# Sheet1.net
KiCad netlist of a schematic drawn in Altium Designer
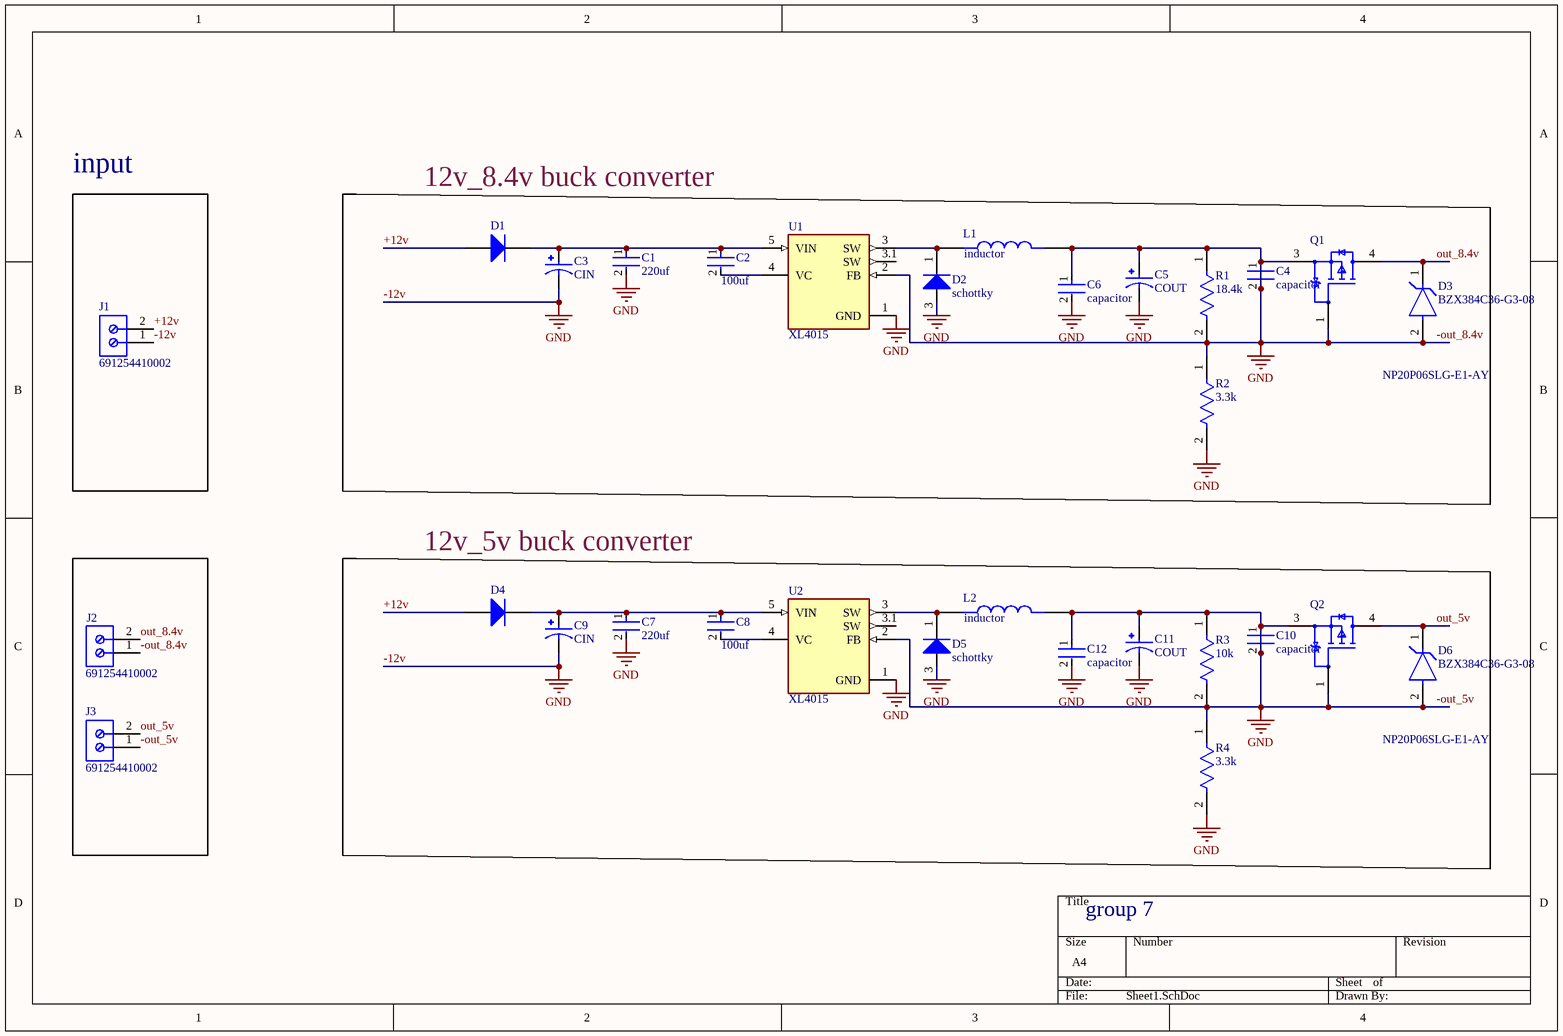
[diagram p0: Sheet1.SchDoc]

(export (version "E")
  (design (tool "Eeschema 10.0.6"))
  (components
    (comp (ref "C1")
      (value "220uf")
      (footprint "FP-GRM43D-0_4-IPC_A")
      (description "Chip Multilayer Ceramic Capacitors for General Purpose, 1812, 0.10uF, X7R, 15%, 10%, 630V")
      (fields (field (name "TOLERANCE") "10%") (field (name "VOLTAGE") "630V"))
      (libsource (lib "Altium Content Vault") (part "02cd4be3c70576c341d710602a673aa"))
    )
    (comp (ref "C2")
      (value "100uf")
      (footprint "FP-GRM43D-0_4-IPC_A")
      (description "Chip Multilayer Ceramic Capacitors for General Purpose, 1812, 0.10uF, X7R, 15%, 10%, 630V")
      (fields (field (name "TOLERANCE") "10%") (field (name "VOLTAGE") "630V"))
      (libsource (lib "Altium Content Vault") (part "02cd4be3c70576c341d710602a673aa"))
    )
    (comp (ref "C3")
      (value "CIN")
      (footprint "CAPPRD500W60D1250H1500:CAPPRD500W60D1250H1500")
      (description "220F 50V Aluminum Electrolytic Capacitors Radial, Can 5000 Hrs @ 105C")
      (fields (field (name "MP") "EEU-FC1H221S") (field (name "MF") "Panasonic Electronic"))
      (libsource (lib "EEUFC1H221S") (part "EEUFC1H221S"))
    )
    (comp (ref "C4")
      (value "capacitor")
      (footprint "FP-GRM43D-0_4-IPC_A")
      (description "Chip Multilayer Ceramic Capacitors for General Purpose, 1812, 0.10uF, X7R, 15%, 10%, 630V")
      (fields (field (name "TOLERANCE") "10%") (field (name "VOLTAGE") "630V"))
      (libsource (lib "Altium Content Vault") (part "02cd4be3c70576c341d710602a673aa"))
    )
    (comp (ref "C5")
      (value "COUT")
      (footprint "CAPPRD500W60D1250H1500:CAPPRD500W60D1250H1500")
      (description "330F 25V Aluminum Electrolytic Capacitors Radial, Can 5000 Hrs @ 105C")
      (fields (field (name "MP") "EEU-FC1H221S") (field (name "MF") "Panasonic Electronic"))
      (libsource (lib "EEUFC1H221S") (part "EEUFC1H221S"))
    )
    (comp (ref "C6")
      (value "capacitor")
      (footprint "FP-GRM43D-0_4-IPC_A")
      (description "Chip Multilayer Ceramic Capacitors for General Purpose, 1812, 0.10uF, X7R, 15%, 10%, 630V")
      (fields (field (name "TOLERANCE") "10%") (field (name "VOLTAGE") "630V"))
      (libsource (lib "Altium Content Vault") (part "02cd4be3c70576c341d710602a673aa"))
    )
    (comp (ref "C7")
      (value "220uf")
      (footprint "FP-GRM43D-0_4-IPC_A")
      (description "Chip Multilayer Ceramic Capacitors for General Purpose, 1812, 0.10uF, X7R, 15%, 10%, 630V")
      (fields (field (name "TOLERANCE") "10%") (field (name "VOLTAGE") "630V"))
      (libsource (lib "Altium Content Vault") (part "02cd4be3c70576c341d710602a673aa"))
    )
    (comp (ref "C8")
      (value "100uf")
      (footprint "FP-GRM43D-0_4-IPC_A")
      (description "Chip Multilayer Ceramic Capacitors for General Purpose, 1812, 0.10uF, X7R, 15%, 10%, 630V")
      (fields (field (name "TOLERANCE") "10%") (field (name "VOLTAGE") "630V"))
      (libsource (lib "Altium Content Vault") (part "02cd4be3c70576c341d710602a673aa"))
    )
    (comp (ref "C9")
      (value "CIN")
      (footprint "CAPPRD500W60D1250H1500:CAPPRD500W60D1250H1500")
      (description "220F 50V Aluminum Electrolytic Capacitors Radial, Can 5000 Hrs @ 105C")
      (fields (field (name "MP") "EEU-FC1H221S") (field (name "MF") "Panasonic Electronic"))
      (libsource (lib "EEUFC1H221S") (part "EEUFC1H221S"))
    )
    (comp (ref "C10")
      (value "capacitor")
      (footprint "FP-GRM43D-0_4-IPC_A")
      (description "Chip Multilayer Ceramic Capacitors for General Purpose, 1812, 0.10uF, X7R, 15%, 10%, 630V")
      (fields (field (name "TOLERANCE") "10%") (field (name "VOLTAGE") "630V"))
      (libsource (lib "Altium Content Vault") (part "02cd4be3c70576c341d710602a673aa"))
    )
    (comp (ref "C11")
      (value "COUT")
      (footprint "CAPPRD500W60D1250H1500:CAPPRD500W60D1250H1500")
      (description "330F 25V Aluminum Electrolytic Capacitors Radial, Can 5000 Hrs @ 105C")
      (fields (field (name "MP") "EEU-FC1H221S") (field (name "MF") "Panasonic Electronic"))
      (libsource (lib "EEUFC1H221S") (part "EEUFC1H221S"))
    )
    (comp (ref "C12")
      (value "capacitor")
      (footprint "FP-GRM43D-0_4-IPC_A")
      (description "Chip Multilayer Ceramic Capacitors for General Purpose, 1812, 0.10uF, X7R, 15%, 10%, 630V")
      (fields (field (name "TOLERANCE") "10%") (field (name "VOLTAGE") "630V"))
      (libsource (lib "Altium Content Vault") (part "02cd4be3c70576c341d710602a673aa"))
    )
    (comp (ref "D1") (value "Diode") (libsource (lib "Simulation Generic Components") (part "Diode")))
    (comp (ref "D2")
      (value "schottky")
      (footprint "ONSC-TO-220-2-221B-04_E")
      (description "SWITCHMODE(TM) Power Rectifier, 2-Pin TO-220, Pb-Free, Tube")
      (fields (field (name "MANUFACTURER") "On Semiconductor") (field (name "PARTNUMBER") "MBR1045G"))
      (libsource (lib "Altium Content Vault") (part "ONSC-D-K1A3-2_A"))
    )
    (comp (ref "D3")
      (value "BZX384C36-G3-08")
      (footprint "FP-S8-V-3910_02-001-MFG")
      (description "BZX384C36-G3-08 Zener Diode Sod3235%, 36V, 0.2W")
      (fields (field (name "TOLERANCE") "5%"))
      (libsource (lib "Altium Content Vault") (part "f813f71cba58e380607f5dd3caf9714"))
    )
    (comp (ref "D4") (value "Diode") (libsource (lib "Simulation Generic Components") (part "Diode")))
    (comp (ref "D5")
      (value "schottky")
      (footprint "ONSC-TO-220-2-221B-04_E")
      (description "SWITCHMODE(TM) Power Rectifier, 2-Pin TO-220, Pb-Free, Tube")
      (fields (field (name "MANUFACTURER") "On Semiconductor") (field (name "PARTNUMBER") "MBR1045G"))
      (libsource (lib "Altium Content Vault") (part "ONSC-D-K1A3-2_A"))
    )
    (comp (ref "D6")
      (value "BZX384C36-G3-08")
      (footprint "FP-S8-V-3910_02-001-MFG")
      (description "BZX384C36-G3-08 Zener Diode Sod3235%, 36V, 0.2W")
      (fields (field (name "TOLERANCE") "5%"))
      (libsource (lib "Altium Content Vault") (part "f813f71cba58e380607f5dd3caf9714"))
    )
    (comp (ref "J1")
      (value "691254410002")
      (footprint "691254410002")
      (libsource (lib "Altium Content Vault") (part "TBL - 1R - 02P - Screw"))
    )
    (comp (ref "J2")
      (value "691254410002")
      (footprint "691254410002")
      (libsource (lib "Altium Content Vault") (part "TBL - 1R - 02P - Screw"))
    )
    (comp (ref "J3")
      (value "691254410002")
      (footprint "691254410002")
      (libsource (lib "Altium Content Vault") (part "TBL - 1R - 02P - Screw"))
    )
    (comp (ref "L1")
      (value "inductor")
      (footprint "IND_XAL6060-223MEC")
      (description "22 ÂµH Shielded Molded Inductor 5 A 60.63mOhm Max Nonstandard")
      (fields (field (name "MF") "Coilcraft") (field (name "MP") "XAL6060-223MEC"))
      (libsource (lib "XAL6060-223MEC") (part "XAL6060-223MEC"))
    )
    (comp (ref "L2")
      (value "inductor")
      (footprint "IND_XAL6060-223MEC")
      (description "22 ÂµH Shielded Molded Inductor 5 A 60.63mOhm Max Nonstandard")
      (fields (field (name "MF") "Coilcraft") (field (name "MP") "XAL6060-223MEC"))
      (libsource (lib "XAL6060-223MEC") (part "XAL6060-223MEC"))
    )
    (comp (ref "Q1")
      (value "NP20P06SLG-E1-AY")
      (footprint "DPAK230P1010X240-3_PRSS0004ZV-A_N")
      (description "Mosfet, P -Ch, 60V, 20A, To-252 Rohs Compliant: Yes")
      (libsource (lib "Altium Content Vault") (part "222bd154d6e9da30f9c87ff774718ca"))
    )
    (comp (ref "Q2")
      (value "NP20P06SLG-E1-AY")
      (footprint "DPAK230P1010X240-3_PRSS0004ZV-A_N")
      (description "Mosfet, P -Ch, 60V, 20A, To-252 Rohs Compliant: Yes")
      (libsource (lib "Altium Content Vault") (part "222bd154d6e9da30f9c87ff774718ca"))
    )
    (comp (ref "R1")
      (value "18.4k")
      (footprint "FP-RN731J-MFG")
      (description "Thin Film Resistors RN 0603 10KΩ 0.1% 10ppm/°C")
      (fields
        (field (name "OCTOPART") "https://octopart.com/rn73c1j10kb-te+connectivity-47108040")
        (field (name "MANUFACTURER") "TE Connectivity")
      )
      (libsource (lib "Altium Content Vault") (part "1029c3af85768c4190bb7ad29bc67b5"))
    )
    (comp (ref "R2")
      (value "3.3k")
      (footprint "FP-RN73R1E-IPC_B")
      (description "3.3kΩ ±1% 0.063W, 1/16W Chip Resistor 0402 (1005 Metric) Moisture Resistant Thin Film")
      (libsource (lib "Altium Content Vault") (part "1029c3af85768c4190bb7ad29bc67b5"))
    )
    (comp (ref "R3")
      (value "10k")
      (footprint "FP-RN731J-MFG")
      (description "Thin Film Resistors RN 0603 10KΩ 0.1% 10ppm/°C")
      (fields
        (field (name "OCTOPART") "https://octopart.com/rn73c1j10kb-te+connectivity-47108040")
        (field (name "MANUFACTURER") "TE Connectivity")
      )
      (libsource (lib "Altium Content Vault") (part "1029c3af85768c4190bb7ad29bc67b5"))
    )
    (comp (ref "R4")
      (value "3.3k")
      (footprint "FP-RN73R1E-IPC_B")
      (description "3.3kΩ ±1% 0.063W, 1/16W Chip Resistor 0402 (1005 Metric) Moisture Resistant Thin Film")
      (libsource (lib "Altium Content Vault") (part "1029c3af85768c4190bb7ad29bc67b5"))
    )
    (comp (ref "U1")
      (value "XL4015")
      (footprint "CONV_XL4015")
      (description "5A 180KHz 36V Buck DC to DC Converter")
      (fields (field (name "MF") "XLSEMI"))
      (libsource (lib "XL4015") (part "XL4015"))
    )
    (comp (ref "U2")
      (value "XL4015")
      (footprint "CONV_XL4015")
      (description "5A 180KHz 36V Buck DC to DC Converter")
      (fields (field (name "MF") "XLSEMI"))
      (libsource (lib "XL4015") (part "XL4015"))
    )
  )
  (nets
    (net (code "1") (name "/+12v") (class "Default")
      (node (ref "D1") (pin "1") (pinfunction "A_1") (pintype "passive"))
      (node (ref "D4") (pin "1") (pinfunction "A_1") (pintype "passive"))
      (node (ref "J1") (pin "2") (pinfunction "2_2") (pintype "passive"))
    )
    (net (code "2") (name "/out_5v") (class "Default")
      (node (ref "D6") (pin "1") (pinfunction "C_1") (pintype "passive"))
      (node (ref "J3") (pin "2") (pinfunction "2_2") (pintype "passive"))
      (node (ref "Q2") (pin "4") (pinfunction "FIN(DRAIN)_4") (pintype "passive"))
    )
    (net (code "3") (name "/out_8.4v") (class "Default")
      (node (ref "D3") (pin "1") (pinfunction "C_1") (pintype "passive"))
      (node (ref "J2") (pin "2") (pinfunction "2_2") (pintype "passive"))
      (node (ref "Q1") (pin "4") (pinfunction "FIN(DRAIN)_4") (pintype "passive"))
    )
    (net (code "4") (name "GND") (class "Default")
      (node (ref "C1") (pin "2") (pinfunction "2_2") (pintype "passive"))
      (node (ref "C10") (pin "1") (pinfunction "1_1") (pintype "passive"))
      (node (ref "C10") (pin "2") (pinfunction "2_2") (pintype "passive"))
      (node (ref "C11") (pin "N") (pinfunction "N_N") (pintype "passive"))
      (node (ref "C11") (pin "P") (pinfunction "P_P") (pintype "passive"))
      (node (ref "C12") (pin "1") (pinfunction "1_1") (pintype "passive"))
      (node (ref "C12") (pin "2") (pinfunction "2_2") (pintype "passive"))
      (node (ref "C3") (pin "N") (pinfunction "N_N") (pintype "passive"))
      (node (ref "C4") (pin "1") (pinfunction "1_1") (pintype "passive"))
      (node (ref "C4") (pin "2") (pinfunction "2_2") (pintype "passive"))
      (node (ref "C5") (pin "N") (pinfunction "N_N") (pintype "passive"))
      (node (ref "C5") (pin "P") (pinfunction "P_P") (pintype "passive"))
      (node (ref "C6") (pin "1") (pinfunction "1_1") (pintype "passive"))
      (node (ref "C6") (pin "2") (pinfunction "2_2") (pintype "passive"))
      (node (ref "C7") (pin "2") (pinfunction "2_2") (pintype "passive"))
      (node (ref "C9") (pin "N") (pinfunction "N_N") (pintype "passive"))
      (node (ref "D2") (pin "3") (pinfunction "A_3") (pintype "passive"))
      (node (ref "D3") (pin "2") (pinfunction "A_2") (pintype "passive"))
      (node (ref "D5") (pin "3") (pinfunction "A_3") (pintype "passive"))
      (node (ref "D6") (pin "2") (pinfunction "A_2") (pintype "passive"))
      (node (ref "J1") (pin "1") (pinfunction "1_1") (pintype "passive"))
      (node (ref "J2") (pin "1") (pinfunction "1_1") (pintype "passive"))
      (node (ref "J3") (pin "1") (pinfunction "1_1") (pintype "passive"))
      (node (ref "L1") (pin "2") (pinfunction "2_2") (pintype "passive"))
      (node (ref "L2") (pin "2") (pinfunction "2_2") (pintype "passive"))
      (node (ref "Q1") (pin "1") (pinfunction "GATE_1") (pintype "passive"))
      (node (ref "Q1") (pin "3") (pinfunction "SOURCE_3") (pintype "passive"))
      (node (ref "Q2") (pin "1") (pinfunction "GATE_1") (pintype "passive"))
      (node (ref "Q2") (pin "3") (pinfunction "SOURCE_3") (pintype "passive"))
      (node (ref "R1") (pin "1") (pinfunction "1_1") (pintype "passive"))
      (node (ref "R1") (pin "2") (pinfunction "2_2") (pintype "passive"))
      (node (ref "R2") (pin "1") (pinfunction "1_1") (pintype "passive"))
      (node (ref "R2") (pin "2") (pinfunction "2_2") (pintype "passive"))
      (node (ref "R3") (pin "1") (pinfunction "1_1") (pintype "passive"))
      (node (ref "R3") (pin "2") (pinfunction "2_2") (pintype "passive"))
      (node (ref "R4") (pin "1") (pinfunction "1_1") (pintype "passive"))
      (node (ref "R4") (pin "2") (pinfunction "2_2") (pintype "passive"))
      (node (ref "U1") (pin "1") (pinfunction "GND_1") (pintype "power_in"))
      (node (ref "U1") (pin "2") (pinfunction "FB_2") (pintype "input"))
      (node (ref "U2") (pin "1") (pinfunction "GND_1") (pintype "power_in"))
      (node (ref "U2") (pin "2") (pinfunction "FB_2") (pintype "input"))
    )
    (net (code "5") (name "Net-(D1-K)") (class "Default")
      (node (ref "C1") (pin "1") (pinfunction "1_1") (pintype "passive"))
      (node (ref "C2") (pin "1") (pinfunction "1_1") (pintype "passive"))
      (node (ref "C3") (pin "P") (pinfunction "P_P") (pintype "passive"))
      (node (ref "D1") (pin "2") (pinfunction "K_2") (pintype "passive"))
      (node (ref "U1") (pin "5") (pinfunction "VIN_5") (pintype "input"))
    )
    (net (code "6") (name "Net-(D2-K)") (class "Default")
      (node (ref "D2") (pin "1") (pinfunction "K_1") (pintype "passive"))
      (node (ref "L1") (pin "1") (pinfunction "1_1") (pintype "passive"))
      (node (ref "U1") (pin "3") (pinfunction "SW_3") (pintype "output"))
    )
    (net (code "7") (name "Net-(D4-K)") (class "Default")
      (node (ref "C7") (pin "1") (pinfunction "1_1") (pintype "passive"))
      (node (ref "C8") (pin "1") (pinfunction "1_1") (pintype "passive"))
      (node (ref "C9") (pin "P") (pinfunction "P_P") (pintype "passive"))
      (node (ref "D4") (pin "2") (pinfunction "K_2") (pintype "passive"))
      (node (ref "U2") (pin "5") (pinfunction "VIN_5") (pintype "input"))
    )
    (net (code "8") (name "Net-(D5-K)") (class "Default")
      (node (ref "D5") (pin "1") (pinfunction "K_1") (pintype "passive"))
      (node (ref "L2") (pin "1") (pinfunction "1_1") (pintype "passive"))
      (node (ref "U2") (pin "3") (pinfunction "SW_3") (pintype "output"))
    )
    (net (code "9") (name "Net-(U1-VC)") (class "Default")
      (node (ref "C2") (pin "2") (pinfunction "2_2") (pintype "passive"))
      (node (ref "U1") (pin "4") (pinfunction "VC_4") (pintype "passive"))
    )
    (net (code "10") (name "Net-(U2-VC)") (class "Default")
      (node (ref "C8") (pin "2") (pinfunction "2_2") (pintype "passive"))
      (node (ref "U2") (pin "4") (pinfunction "VC_4") (pintype "passive"))
    )
    (net (code "11") (name "unconnected-(U1-SW-Pad3.1)") (class "Default")
      (node (ref "U1") (pin "3.1") (pinfunction "SW_3.1") (pintype "output"))
    )
    (net (code "12") (name "unconnected-(U2-SW-Pad3.1)") (class "Default")
      (node (ref "U2") (pin "3.1") (pinfunction "SW_3.1") (pintype "output"))
    )
  )
)
